# sub_2021-12-09.net
KiCad netlist of a schematic drawn in Altium Designer
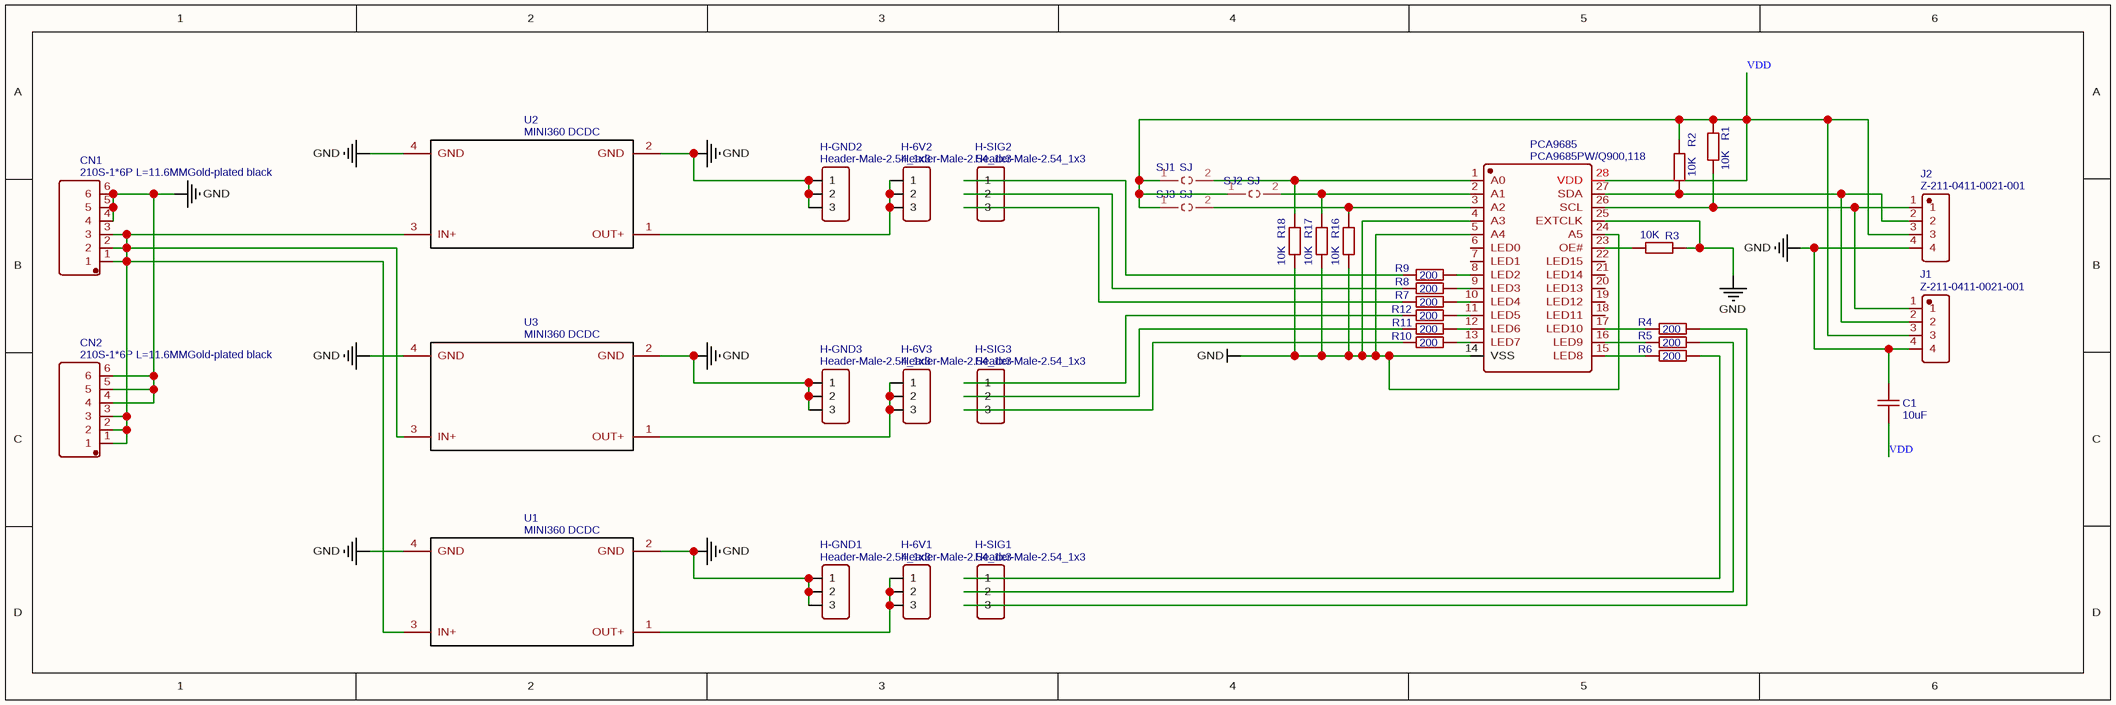
[diagram p0: sub_2021-12-09.schdoc]

(export (version "E")
  (design (tool "Eeschema 10.0.6"))
  (components
    (comp (ref "C1")
      (value "10uF")
      (fields
        (field (name "BOM_SUPPLIER PART") "C329933")
        (field (name "BOM_MANUFACTURER PART") "C2012X5R1E106KT000N")
        (field (name "CONTRIBUTOR") "LCSC")
      )
      (libsource (lib "altium-import") (part "root_0_10uF_"))
    )
    (comp (ref "CN1")
      (value "210S-1*6P L=11.6MMGold-plated black")
      (fields (field (name "BOM_SUPPLIER PART") "C124380") (field (name "CONTRIBUTOR") "LCSC"))
      (libsource (lib "altium-import") (part "root_2_210S-1*6P L=11.6MMGold-plated black_"))
    )
    (comp (ref "CN2")
      (value "210S-1*6P L=11.6MMGold-plated black")
      (fields (field (name "BOM_SUPPLIER PART") "C124380") (field (name "CONTRIBUTOR") "LCSC"))
      (libsource (lib "altium-import") (part "root_2_210S-1*6P L=11.6MMGold-plated black_"))
    )
    (comp (ref "H-6V1")
      (value "Header-Male-2.54_1x3")
      (fields
        (field (name "BOM_MANUFACTURER PART") "Header2.54mm 1*3P")
        (field (name "BOM_SUPPLIER PART") "C49257")
      )
      (libsource (lib "altium-import") (part "root_0_Header-Male-2.54_1x3_"))
    )
    (comp (ref "H-6V2")
      (value "Header-Male-2.54_1x3")
      (fields
        (field (name "BOM_MANUFACTURER PART") "Header2.54mm 1*3P")
        (field (name "BOM_SUPPLIER PART") "C49257")
      )
      (libsource (lib "altium-import") (part "root_0_Header-Male-2.54_1x3_"))
    )
    (comp (ref "H-6V3")
      (value "Header-Male-2.54_1x3")
      (fields
        (field (name "BOM_MANUFACTURER PART") "Header2.54mm 1*3P")
        (field (name "BOM_SUPPLIER PART") "C49257")
      )
      (libsource (lib "altium-import") (part "root_0_Header-Male-2.54_1x3_"))
    )
    (comp (ref "H-GND1")
      (value "Header-Male-2.54_1x3")
      (fields
        (field (name "BOM_MANUFACTURER PART") "Header2.54mm 1*3P")
        (field (name "BOM_SUPPLIER PART") "C49257")
      )
      (libsource (lib "altium-import") (part "root_0_Header-Male-2.54_1x3_"))
    )
    (comp (ref "H-GND2")
      (value "Header-Male-2.54_1x3")
      (fields
        (field (name "BOM_MANUFACTURER PART") "Header2.54mm 1*3P")
        (field (name "BOM_SUPPLIER PART") "C49257")
      )
      (libsource (lib "altium-import") (part "root_0_Header-Male-2.54_1x3_"))
    )
    (comp (ref "H-GND3")
      (value "Header-Male-2.54_1x3")
      (fields
        (field (name "BOM_MANUFACTURER PART") "Header2.54mm 1*3P")
        (field (name "BOM_SUPPLIER PART") "C49257")
      )
      (libsource (lib "altium-import") (part "root_0_Header-Male-2.54_1x3_"))
    )
    (comp (ref "H-SIG1")
      (value "Header-Male-2.54_1x3")
      (fields
        (field (name "BOM_MANUFACTURER PART") "Header2.54mm 1*3P")
        (field (name "BOM_SUPPLIER PART") "C49257")
      )
      (libsource (lib "altium-import") (part "root_0_Header-Male-2.54_1x3_"))
    )
    (comp (ref "H-SIG2")
      (value "Header-Male-2.54_1x3")
      (fields
        (field (name "BOM_MANUFACTURER PART") "Header2.54mm 1*3P")
        (field (name "BOM_SUPPLIER PART") "C49257")
      )
      (libsource (lib "altium-import") (part "root_0_Header-Male-2.54_1x3_"))
    )
    (comp (ref "H-SIG3")
      (value "Header-Male-2.54_1x3")
      (fields
        (field (name "BOM_MANUFACTURER PART") "Header2.54mm 1*3P")
        (field (name "BOM_SUPPLIER PART") "C49257")
      )
      (libsource (lib "altium-import") (part "root_0_Header-Male-2.54_1x3_"))
    )
    (comp (ref "J1")
      (value "Z-211-0411-0021-001")
      (fields (field (name "BOM_SUPPLIER PART") "C152150") (field (name "CONTRIBUTOR") "LCSC"))
      (libsource (lib "altium-import") (part "root_0_Z-211-0411-0021-001_"))
    )
    (comp (ref "J2")
      (value "Z-211-0411-0021-001")
      (fields (field (name "BOM_SUPPLIER PART") "C152150") (field (name "CONTRIBUTOR") "LCSC"))
      (libsource (lib "altium-import") (part "root_0_Z-211-0411-0021-001_"))
    )
    (comp (ref "PCA9685")
      (value "PCA9685PW/Q900,118")
      (fields (field (name "BOM_SUPPLIER PART") "C92206"))
      (libsource (lib "altium-import") (part "root_0_PCA9685PW/Q900,118_"))
    )
    (comp (ref "R1")
      (value "10K")
      (fields
        (field (name "BOM_SUPPLIER PART") "C238881")
        (field (name "BOM_MANUFACTURER PART") "RMCF0603JT10K0")
        (field (name "CONTRIBUTOR") "LCSC")
      )
      (libsource (lib "altium-import") (part "root_3_10K_"))
    )
    (comp (ref "R2")
      (value "10K")
      (fields
        (field (name "BOM_SUPPLIER PART") "C238881")
        (field (name "BOM_MANUFACTURER PART") "RMCF0603JT10K0")
        (field (name "CONTRIBUTOR") "LCSC")
      )
      (libsource (lib "altium-import") (part "root_3_10K_"))
    )
    (comp (ref "R3")
      (value "10K")
      (fields
        (field (name "BOM_SUPPLIER PART") "C238881")
        (field (name "BOM_MANUFACTURER PART") "RMCF0603JT10K0")
        (field (name "CONTRIBUTOR") "LCSC")
      )
      (libsource (lib "altium-import") (part "root_2_10K_"))
    )
    (comp (ref "R4")
      (value "200")
      (fields
        (field (name "BOM_SUPPLIER PART") "C209065")
        (field (name "BOM_MANUFACTURER PART") "RMS06FT2000")
        (field (name "CONTRIBUTOR") "LCSC")
      )
      (libsource (lib "altium-import") (part "root_0_200_"))
    )
    (comp (ref "R5")
      (value "200")
      (fields
        (field (name "BOM_SUPPLIER PART") "C209065")
        (field (name "BOM_MANUFACTURER PART") "RMS06FT2000")
        (field (name "CONTRIBUTOR") "LCSC")
      )
      (libsource (lib "altium-import") (part "root_0_200_"))
    )
    (comp (ref "R6")
      (value "200")
      (fields
        (field (name "BOM_SUPPLIER PART") "C209065")
        (field (name "BOM_MANUFACTURER PART") "RMS06FT2000")
        (field (name "CONTRIBUTOR") "LCSC")
      )
      (libsource (lib "altium-import") (part "root_0_200_"))
    )
    (comp (ref "R7")
      (value "200")
      (fields
        (field (name "BOM_SUPPLIER PART") "C209065")
        (field (name "BOM_MANUFACTURER PART") "RMS06FT2000")
        (field (name "CONTRIBUTOR") "LCSC")
      )
      (libsource (lib "altium-import") (part "root_0_200_"))
    )
    (comp (ref "R8")
      (value "200")
      (fields
        (field (name "BOM_SUPPLIER PART") "C209065")
        (field (name "BOM_MANUFACTURER PART") "RMS06FT2000")
        (field (name "CONTRIBUTOR") "LCSC")
      )
      (libsource (lib "altium-import") (part "root_0_200_"))
    )
    (comp (ref "R9")
      (value "200")
      (fields
        (field (name "BOM_SUPPLIER PART") "C209065")
        (field (name "BOM_MANUFACTURER PART") "RMS06FT2000")
        (field (name "CONTRIBUTOR") "LCSC")
      )
      (libsource (lib "altium-import") (part "root_0_200_"))
    )
    (comp (ref "R10")
      (value "200")
      (fields
        (field (name "BOM_SUPPLIER PART") "C209065")
        (field (name "BOM_MANUFACTURER PART") "RMS06FT2000")
        (field (name "CONTRIBUTOR") "LCSC")
      )
      (libsource (lib "altium-import") (part "root_0_200_"))
    )
    (comp (ref "R11")
      (value "200")
      (fields
        (field (name "BOM_SUPPLIER PART") "C209065")
        (field (name "BOM_MANUFACTURER PART") "RMS06FT2000")
        (field (name "CONTRIBUTOR") "LCSC")
      )
      (libsource (lib "altium-import") (part "root_0_200_"))
    )
    (comp (ref "R12")
      (value "200")
      (fields
        (field (name "BOM_SUPPLIER PART") "C209065")
        (field (name "BOM_MANUFACTURER PART") "RMS06FT2000")
        (field (name "CONTRIBUTOR") "LCSC")
      )
      (libsource (lib "altium-import") (part "root_0_200_"))
    )
    (comp (ref "R16")
      (value "10K")
      (fields
        (field (name "BOM_SUPPLIER PART") "C238881")
        (field (name "BOM_MANUFACTURER PART") "RMCF0603JT10K0")
        (field (name "CONTRIBUTOR") "LCSC")
      )
      (libsource (lib "altium-import") (part "root_1_10K_"))
    )
    (comp (ref "R17")
      (value "10K")
      (fields
        (field (name "BOM_SUPPLIER PART") "C238881")
        (field (name "BOM_MANUFACTURER PART") "RMCF0603JT10K0")
        (field (name "CONTRIBUTOR") "LCSC")
      )
      (libsource (lib "altium-import") (part "root_1_10K_"))
    )
    (comp (ref "R18")
      (value "10K")
      (fields
        (field (name "BOM_SUPPLIER PART") "C238881")
        (field (name "BOM_MANUFACTURER PART") "RMCF0603JT10K0")
        (field (name "CONTRIBUTOR") "LCSC")
      )
      (libsource (lib "altium-import") (part "root_1_10K_"))
    )
    (comp (ref "SJ1")
      (value "SJ")
      (fields (field (name "CONTRIBUTOR") "Zealot"))
      (libsource (lib "altium-import") (part "root_0_SJ_"))
    )
    (comp (ref "SJ2")
      (value "SJ")
      (fields (field (name "CONTRIBUTOR") "Zealot"))
      (libsource (lib "altium-import") (part "root_0_SJ_"))
    )
    (comp (ref "SJ3")
      (value "SJ")
      (fields (field (name "CONTRIBUTOR") "Zealot"))
      (libsource (lib "altium-import") (part "root_0_SJ_"))
    )
    (comp (ref "U1")
      (value "MINI360 DCDC")
      (fields (field (name "CONTRIBUTOR") "libc0607"))
      (libsource (lib "altium-import") (part "root_2_MINI360 DCDC_"))
    )
    (comp (ref "U2")
      (value "MINI360 DCDC")
      (fields (field (name "CONTRIBUTOR") "libc0607"))
      (libsource (lib "altium-import") (part "root_2_MINI360 DCDC_"))
    )
    (comp (ref "U3")
      (value "MINI360 DCDC")
      (fields (field (name "CONTRIBUTOR") "libc0607"))
      (libsource (lib "altium-import") (part "root_2_MINI360 DCDC_"))
    )
  )
  (nets
    (net (code "1") (name "/VDD") (class "Default")
      (node (ref "C1") (pin "2") (pinfunction "2_2") (pintype "passive"))
      (node (ref "J1") (pin "3") (pinfunction "3_3") (pintype "passive"))
      (node (ref "J2") (pin "3") (pinfunction "3_3") (pintype "passive"))
      (node (ref "PCA9685") (pin "28") (pinfunction "VDD_28") (pintype "passive"))
      (node (ref "R1") (pin "1") (pinfunction "1_1") (pintype "passive"))
      (node (ref "R2") (pin "1") (pinfunction "1_1") (pintype "passive"))
      (node (ref "SJ1") (pin "1") (pinfunction "1_1") (pintype "passive"))
      (node (ref "SJ2") (pin "1") (pinfunction "1_1") (pintype "passive"))
      (node (ref "SJ3") (pin "1") (pinfunction "1_1") (pintype "passive"))
    )
    (net (code "2") (name "GND") (class "Default")
      (node (ref "C1") (pin "1") (pinfunction "1_1") (pintype "passive"))
      (node (ref "CN1") (pin "4") (pinfunction "4_4") (pintype "passive"))
      (node (ref "CN1") (pin "5") (pinfunction "5_5") (pintype "passive"))
      (node (ref "CN1") (pin "6") (pinfunction "6_6") (pintype "passive"))
      (node (ref "CN2") (pin "4") (pinfunction "4_4") (pintype "passive"))
      (node (ref "CN2") (pin "5") (pinfunction "5_5") (pintype "passive"))
      (node (ref "CN2") (pin "6") (pinfunction "6_6") (pintype "passive"))
      (node (ref "H-GND1") (pin "1") (pinfunction "1_1") (pintype "passive"))
      (node (ref "H-GND1") (pin "2") (pinfunction "2_2") (pintype "passive"))
      (node (ref "H-GND1") (pin "3") (pinfunction "3_3") (pintype "passive"))
      (node (ref "H-GND2") (pin "1") (pinfunction "1_1") (pintype "passive"))
      (node (ref "H-GND2") (pin "2") (pinfunction "2_2") (pintype "passive"))
      (node (ref "H-GND2") (pin "3") (pinfunction "3_3") (pintype "passive"))
      (node (ref "H-GND3") (pin "1") (pinfunction "1_1") (pintype "passive"))
      (node (ref "H-GND3") (pin "2") (pinfunction "2_2") (pintype "passive"))
      (node (ref "H-GND3") (pin "3") (pinfunction "3_3") (pintype "passive"))
      (node (ref "J1") (pin "4") (pinfunction "4_4") (pintype "passive"))
      (node (ref "J2") (pin "4") (pinfunction "4_4") (pintype "passive"))
      (node (ref "PCA9685") (pin "14") (pinfunction "VSS_14") (pintype "passive"))
      (node (ref "PCA9685") (pin "24") (pinfunction "A5_24") (pintype "passive"))
      (node (ref "PCA9685") (pin "25") (pinfunction "EXTCLK_25") (pintype "passive"))
      (node (ref "PCA9685") (pin "4") (pinfunction "A3_4") (pintype "passive"))
      (node (ref "PCA9685") (pin "5") (pinfunction "A4_5") (pintype "passive"))
      (node (ref "R16") (pin "1") (pinfunction "1_1") (pintype "passive"))
      (node (ref "R17") (pin "1") (pinfunction "1_1") (pintype "passive"))
      (node (ref "R18") (pin "1") (pinfunction "1_1") (pintype "passive"))
      (node (ref "R3") (pin "1") (pinfunction "1_1") (pintype "passive"))
      (node (ref "U1") (pin "2") (pinfunction "GND_2") (pintype "passive"))
      (node (ref "U1") (pin "4") (pinfunction "GND_4") (pintype "passive"))
      (node (ref "U2") (pin "2") (pinfunction "GND_2") (pintype "passive"))
      (node (ref "U2") (pin "4") (pinfunction "GND_4") (pintype "passive"))
      (node (ref "U3") (pin "2") (pinfunction "GND_2") (pintype "passive"))
      (node (ref "U3") (pin "4") (pinfunction "GND_4") (pintype "passive"))
    )
    (net (code "3") (name "Net-(H-SIG1-Pad1)") (class "Default")
      (node (ref "H-SIG1") (pin "1") (pinfunction "1_1") (pintype "passive"))
      (node (ref "R6") (pin "2") (pinfunction "2_2") (pintype "passive"))
    )
    (net (code "4") (name "Net-(H-SIG1-Pad2)") (class "Default")
      (node (ref "H-SIG1") (pin "2") (pinfunction "2_2") (pintype "passive"))
      (node (ref "R5") (pin "2") (pinfunction "2_2") (pintype "passive"))
    )
    (net (code "5") (name "Net-(H-SIG1-Pad3)") (class "Default")
      (node (ref "H-SIG1") (pin "3") (pinfunction "3_3") (pintype "passive"))
      (node (ref "R4") (pin "2") (pinfunction "2_2") (pintype "passive"))
    )
    (net (code "6") (name "Net-(H-SIG2-Pad1)") (class "Default")
      (node (ref "H-SIG2") (pin "1") (pinfunction "1_1") (pintype "passive"))
      (node (ref "R9") (pin "1") (pinfunction "1_1") (pintype "passive"))
    )
    (net (code "7") (name "Net-(H-SIG2-Pad2)") (class "Default")
      (node (ref "H-SIG2") (pin "2") (pinfunction "2_2") (pintype "passive"))
      (node (ref "R8") (pin "1") (pinfunction "1_1") (pintype "passive"))
    )
    (net (code "8") (name "Net-(H-SIG2-Pad3)") (class "Default")
      (node (ref "H-SIG2") (pin "3") (pinfunction "3_3") (pintype "passive"))
      (node (ref "R7") (pin "1") (pinfunction "1_1") (pintype "passive"))
    )
    (net (code "9") (name "Net-(H-SIG3-Pad1)") (class "Default")
      (node (ref "H-SIG3") (pin "1") (pinfunction "1_1") (pintype "passive"))
      (node (ref "R12") (pin "1") (pinfunction "1_1") (pintype "passive"))
    )
    (net (code "10") (name "Net-(H-SIG3-Pad2)") (class "Default")
      (node (ref "H-SIG3") (pin "2") (pinfunction "2_2") (pintype "passive"))
      (node (ref "R11") (pin "1") (pinfunction "1_1") (pintype "passive"))
    )
    (net (code "11") (name "Net-(H-SIG3-Pad3)") (class "Default")
      (node (ref "H-SIG3") (pin "3") (pinfunction "3_3") (pintype "passive"))
      (node (ref "R10") (pin "1") (pinfunction "1_1") (pintype "passive"))
    )
    (net (code "12") (name "Net-(PCA9685-A0)") (class "Default")
      (node (ref "PCA9685") (pin "1") (pinfunction "A0_1") (pintype "passive"))
      (node (ref "R18") (pin "2") (pinfunction "2_2") (pintype "passive"))
      (node (ref "SJ1") (pin "2") (pinfunction "2_2") (pintype "passive"))
    )
    (net (code "13") (name "Net-(PCA9685-A1)") (class "Default")
      (node (ref "PCA9685") (pin "2") (pinfunction "A1_2") (pintype "passive"))
      (node (ref "R17") (pin "2") (pinfunction "2_2") (pintype "passive"))
      (node (ref "SJ2") (pin "2") (pinfunction "2_2") (pintype "passive"))
    )
    (net (code "14") (name "Net-(PCA9685-A2)") (class "Default")
      (node (ref "PCA9685") (pin "3") (pinfunction "A2_3") (pintype "passive"))
      (node (ref "R16") (pin "2") (pinfunction "2_2") (pintype "passive"))
      (node (ref "SJ3") (pin "2") (pinfunction "2_2") (pintype "passive"))
    )
    (net (code "15") (name "Net-(PCA9685-LED2)") (class "Default")
      (node (ref "PCA9685") (pin "8") (pinfunction "LED2_8") (pintype "passive"))
      (node (ref "R9") (pin "2") (pinfunction "2_2") (pintype "passive"))
    )
    (net (code "16") (name "Net-(PCA9685-LED3)") (class "Default")
      (node (ref "PCA9685") (pin "9") (pinfunction "LED3_9") (pintype "passive"))
      (node (ref "R8") (pin "2") (pinfunction "2_2") (pintype "passive"))
    )
    (net (code "17") (name "Net-(PCA9685-LED4)") (class "Default")
      (node (ref "PCA9685") (pin "10") (pinfunction "LED4_10") (pintype "passive"))
      (node (ref "R7") (pin "2") (pinfunction "2_2") (pintype "passive"))
    )
    (net (code "18") (name "Net-(PCA9685-LED5)") (class "Default")
      (node (ref "PCA9685") (pin "11") (pinfunction "LED5_11") (pintype "passive"))
      (node (ref "R12") (pin "2") (pinfunction "2_2") (pintype "passive"))
    )
    (net (code "19") (name "Net-(PCA9685-LED6)") (class "Default")
      (node (ref "PCA9685") (pin "12") (pinfunction "LED6_12") (pintype "passive"))
      (node (ref "R11") (pin "2") (pinfunction "2_2") (pintype "passive"))
    )
    (net (code "20") (name "Net-(PCA9685-LED7)") (class "Default")
      (node (ref "PCA9685") (pin "13") (pinfunction "LED7_13") (pintype "passive"))
      (node (ref "R10") (pin "2") (pinfunction "2_2") (pintype "passive"))
    )
    (net (code "21") (name "Net-(PCA9685-LED8)") (class "Default")
      (node (ref "PCA9685") (pin "15") (pinfunction "LED8_15") (pintype "passive"))
      (node (ref "R6") (pin "1") (pinfunction "1_1") (pintype "passive"))
    )
    (net (code "22") (name "Net-(PCA9685-LED9)") (class "Default")
      (node (ref "PCA9685") (pin "16") (pinfunction "LED9_16") (pintype "passive"))
      (node (ref "R5") (pin "1") (pinfunction "1_1") (pintype "passive"))
    )
    (net (code "23") (name "Net-(PCA9685-LED10)") (class "Default")
      (node (ref "PCA9685") (pin "17") (pinfunction "LED10_17") (pintype "passive"))
      (node (ref "R4") (pin "1") (pinfunction "1_1") (pintype "passive"))
    )
    (net (code "24") (name "Net-(PCA9685-OE#)") (class "Default")
      (node (ref "PCA9685") (pin "23") (pinfunction "OE#_23") (pintype "passive"))
      (node (ref "R3") (pin "2") (pinfunction "2_2") (pintype "passive"))
    )
    (net (code "25") (name "Net-(PCA9685-SCL)") (class "Default")
      (node (ref "J1") (pin "1") (pinfunction "1_1") (pintype "passive"))
      (node (ref "J2") (pin "1") (pinfunction "1_1") (pintype "passive"))
      (node (ref "PCA9685") (pin "26") (pinfunction "SCL_26") (pintype "passive"))
      (node (ref "R1") (pin "2") (pinfunction "2_2") (pintype "passive"))
    )
    (net (code "26") (name "Net-(PCA9685-SDA)") (class "Default")
      (node (ref "J1") (pin "2") (pinfunction "2_2") (pintype "passive"))
      (node (ref "J2") (pin "2") (pinfunction "2_2") (pintype "passive"))
      (node (ref "PCA9685") (pin "27") (pinfunction "SDA_27") (pintype "passive"))
      (node (ref "R2") (pin "2") (pinfunction "2_2") (pintype "passive"))
    )
    (net (code "27") (name "Net-(U1-IN+)") (class "Default")
      (node (ref "CN1") (pin "1") (pinfunction "1_1") (pintype "passive"))
      (node (ref "CN1") (pin "2") (pinfunction "2_2") (pintype "passive"))
      (node (ref "CN1") (pin "3") (pinfunction "3_3") (pintype "passive"))
      (node (ref "CN2") (pin "1") (pinfunction "1_1") (pintype "passive"))
      (node (ref "CN2") (pin "2") (pinfunction "2_2") (pintype "passive"))
      (node (ref "CN2") (pin "3") (pinfunction "3_3") (pintype "passive"))
      (node (ref "U1") (pin "3") (pinfunction "IN+_3") (pintype "passive"))
      (node (ref "U2") (pin "3") (pinfunction "IN+_3") (pintype "passive"))
      (node (ref "U3") (pin "3") (pinfunction "IN+_3") (pintype "passive"))
    )
    (net (code "28") (name "Net-(U1-OUT+)") (class "Default")
      (node (ref "H-6V1") (pin "1") (pinfunction "1_1") (pintype "passive"))
      (node (ref "H-6V1") (pin "2") (pinfunction "2_2") (pintype "passive"))
      (node (ref "H-6V1") (pin "3") (pinfunction "3_3") (pintype "passive"))
      (node (ref "U1") (pin "1") (pinfunction "OUT+_1") (pintype "passive"))
    )
    (net (code "29") (name "Net-(U2-OUT+)") (class "Default")
      (node (ref "H-6V2") (pin "1") (pinfunction "1_1") (pintype "passive"))
      (node (ref "H-6V2") (pin "2") (pinfunction "2_2") (pintype "passive"))
      (node (ref "H-6V2") (pin "3") (pinfunction "3_3") (pintype "passive"))
      (node (ref "U2") (pin "1") (pinfunction "OUT+_1") (pintype "passive"))
    )
    (net (code "30") (name "Net-(U3-OUT+)") (class "Default")
      (node (ref "H-6V3") (pin "1") (pinfunction "1_1") (pintype "passive"))
      (node (ref "H-6V3") (pin "2") (pinfunction "2_2") (pintype "passive"))
      (node (ref "H-6V3") (pin "3") (pinfunction "3_3") (pintype "passive"))
      (node (ref "U3") (pin "1") (pinfunction "OUT+_1") (pintype "passive"))
    )
    (net (code "31") (name "unconnected-(PCA9685-LED0-Pad6)") (class "Default")
      (node (ref "PCA9685") (pin "6") (pinfunction "LED0_6") (pintype "passive"))
    )
    (net (code "32") (name "unconnected-(PCA9685-LED1-Pad7)") (class "Default")
      (node (ref "PCA9685") (pin "7") (pinfunction "LED1_7") (pintype "passive"))
    )
    (net (code "33") (name "unconnected-(PCA9685-LED11-Pad18)") (class "Default")
      (node (ref "PCA9685") (pin "18") (pinfunction "LED11_18") (pintype "passive"))
    )
    (net (code "34") (name "unconnected-(PCA9685-LED12-Pad19)") (class "Default")
      (node (ref "PCA9685") (pin "19") (pinfunction "LED12_19") (pintype "passive"))
    )
    (net (code "35") (name "unconnected-(PCA9685-LED13-Pad20)") (class "Default")
      (node (ref "PCA9685") (pin "20") (pinfunction "LED13_20") (pintype "passive"))
    )
    (net (code "36") (name "unconnected-(PCA9685-LED14-Pad21)") (class "Default")
      (node (ref "PCA9685") (pin "21") (pinfunction "LED14_21") (pintype "passive"))
    )
    (net (code "37") (name "unconnected-(PCA9685-LED15-Pad22)") (class "Default")
      (node (ref "PCA9685") (pin "22") (pinfunction "LED15_22") (pintype "passive"))
    )
  )
)
